# v2164_quad_VCA_0402_DIL.net
KiCad netlist of a schematic drawn in EAGLE
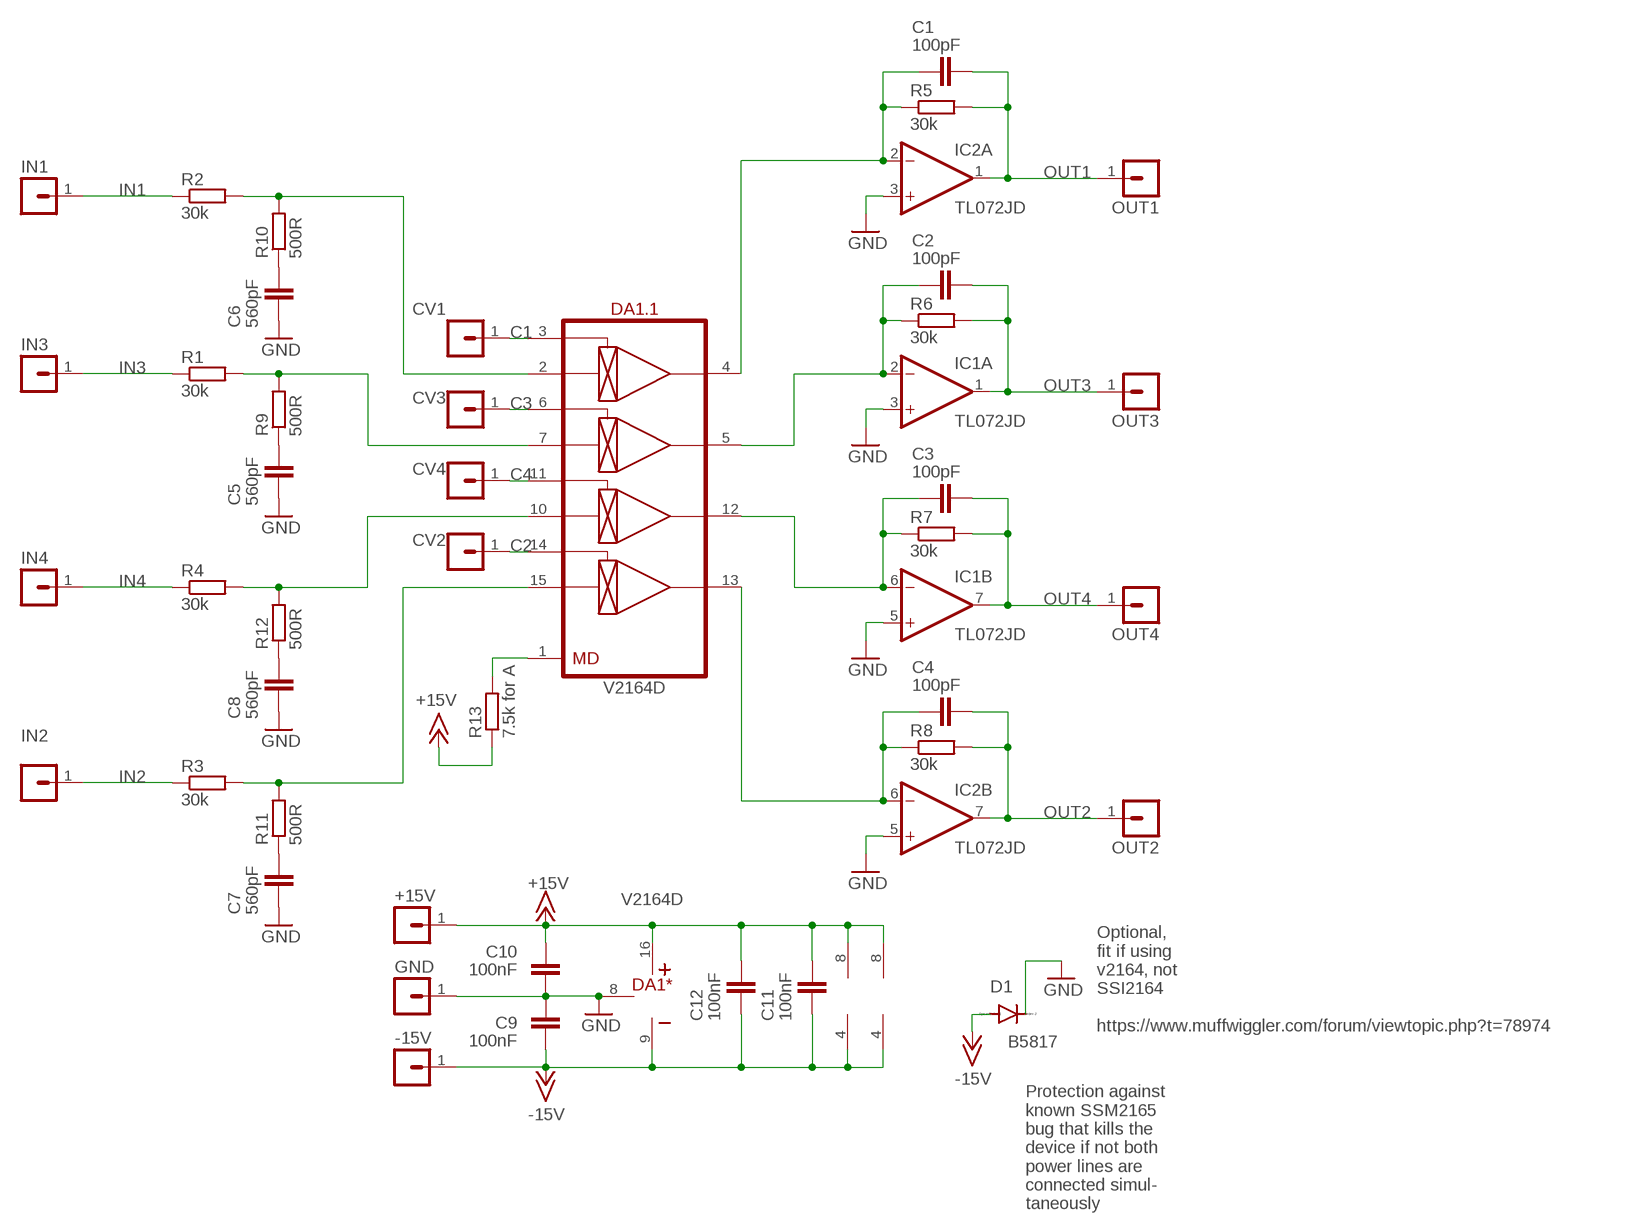
[diagram p0: schematic, sheet 1]

(export (version "E")
  (design (tool "Eeschema 10.0.6"))
  (components
    (comp (ref "+15V")
      (value "MA01-1JP")
      (footprint "eagle-import:SIP-PIN01-1J")
      (libsource (lib "eagle-import") (part "MA01-1JP"))
    )
    (comp (ref "-15V")
      (value "MA01-1JP")
      (footprint "eagle-import:SIP-PIN01-1J")
      (libsource (lib "eagle-import") (part "MA01-1JP"))
    )
    (comp (ref "C1")
      (value "100pF")
      (footprint "eagle-import:C0402")
      (libsource (lib "eagle-import") (part "C-EUC0402"))
    )
    (comp (ref "C2")
      (value "100pF")
      (footprint "eagle-import:C0402")
      (libsource (lib "eagle-import") (part "C-EUC0402"))
    )
    (comp (ref "C3")
      (value "100pF")
      (footprint "eagle-import:C0402")
      (libsource (lib "eagle-import") (part "C-EUC0402"))
    )
    (comp (ref "C4")
      (value "100pF")
      (footprint "eagle-import:C0402")
      (libsource (lib "eagle-import") (part "C-EUC0402"))
    )
    (comp (ref "C5")
      (value "560pF")
      (footprint "eagle-import:C0603")
      (libsource (lib "eagle-import") (part "C-EUC0603"))
    )
    (comp (ref "C6")
      (value "560pF")
      (footprint "eagle-import:C0603")
      (libsource (lib "eagle-import") (part "C-EUC0603"))
    )
    (comp (ref "C7")
      (value "560pF")
      (footprint "eagle-import:C0603")
      (libsource (lib "eagle-import") (part "C-EUC0603"))
    )
    (comp (ref "C8")
      (value "560pF")
      (footprint "eagle-import:C0603")
      (libsource (lib "eagle-import") (part "C-EUC0603"))
    )
    (comp (ref "C9")
      (value "100nF")
      (footprint "eagle-import:C0402")
      (libsource (lib "eagle-import") (part "C-EUC0402"))
    )
    (comp (ref "C10")
      (value "100nF")
      (footprint "eagle-import:C0402")
      (libsource (lib "eagle-import") (part "C-EUC0402"))
    )
    (comp (ref "C11")
      (value "100nF")
      (footprint "eagle-import:C0402")
      (libsource (lib "eagle-import") (part "C-EUC0402"))
    )
    (comp (ref "C12")
      (value "100nF")
      (footprint "eagle-import:C0402")
      (libsource (lib "eagle-import") (part "C-EUC0402"))
    )
    (comp (ref "CV1")
      (value "MA01-1JP")
      (footprint "eagle-import:SIP-PIN01-1J")
      (libsource (lib "eagle-import") (part "MA01-1JP"))
    )
    (comp (ref "CV2")
      (value "MA01-1JP")
      (footprint "eagle-import:SIP-PIN01-1J")
      (libsource (lib "eagle-import") (part "MA01-1JP"))
    )
    (comp (ref "CV3")
      (value "MA01-1JP")
      (footprint "eagle-import:SIP-PIN01-1J")
      (libsource (lib "eagle-import") (part "MA01-1JP"))
    )
    (comp (ref "CV4")
      (value "MA01-1JP")
      (footprint "eagle-import:SIP-PIN01-1J")
      (libsource (lib "eagle-import") (part "MA01-1JP"))
    )
    (comp (ref "D1")
      (value "B5817")
      (footprint "eagle-import:SOD323-R")
      (libsource (lib "eagle-import") (part "DIODE-SOD323-R"))
    )
    (comp (ref "DA1")
      (value "V2164D")
      (footprint "eagle-import:DIP-16")
      (libsource (lib "eagle-import") (part "V2164D"))
    )
    (comp (ref "GND")
      (value "MA01-1JP")
      (footprint "eagle-import:SIP-PIN01-1J")
      (libsource (lib "eagle-import") (part "MA01-1JP"))
    )
    (comp (ref "IC1")
      (value "TL072JD")
      (footprint "eagle-import:SO08J")
      (libsource (lib "eagle-import") (part "TL072JD"))
    )
    (comp (ref "IC2")
      (value "TL072JD")
      (footprint "eagle-import:SO08J")
      (libsource (lib "eagle-import") (part "TL072JD"))
    )
    (comp (ref "IN1")
      (value "MA01-1JP")
      (footprint "eagle-import:SIP-PIN01-1J")
      (libsource (lib "eagle-import") (part "MA01-1JP"))
    )
    (comp (ref "IN2")
      (value "MA01-1JP")
      (footprint "eagle-import:SIP-PIN01-1J")
      (libsource (lib "eagle-import") (part "MA01-1JP"))
    )
    (comp (ref "IN3")
      (value "MA01-1JP")
      (footprint "eagle-import:SIP-PIN01-1J")
      (libsource (lib "eagle-import") (part "MA01-1JP"))
    )
    (comp (ref "IN4")
      (value "MA01-1JP")
      (footprint "eagle-import:SIP-PIN01-1J")
      (libsource (lib "eagle-import") (part "MA01-1JP"))
    )
    (comp (ref "OUT1")
      (value "MA01-1JP")
      (footprint "eagle-import:SIP-PIN01-1J")
      (libsource (lib "eagle-import") (part "MA01-1JP"))
    )
    (comp (ref "OUT2")
      (value "MA01-1JP")
      (footprint "eagle-import:SIP-PIN01-1J")
      (libsource (lib "eagle-import") (part "MA01-1JP"))
    )
    (comp (ref "OUT3")
      (value "MA01-1JP")
      (footprint "eagle-import:SIP-PIN01-1J")
      (libsource (lib "eagle-import") (part "MA01-1JP"))
    )
    (comp (ref "OUT4")
      (value "MA01-1JP")
      (footprint "eagle-import:SIP-PIN01-1J")
      (libsource (lib "eagle-import") (part "MA01-1JP"))
    )
    (comp (ref "R1")
      (value "30k")
      (footprint "eagle-import:R0402")
      (libsource (lib "eagle-import") (part "R-EU_R0402"))
    )
    (comp (ref "R2")
      (value "30k")
      (footprint "eagle-import:R0402")
      (libsource (lib "eagle-import") (part "R-EU_R0402"))
    )
    (comp (ref "R3")
      (value "30k")
      (footprint "eagle-import:R0402")
      (libsource (lib "eagle-import") (part "R-EU_R0402"))
    )
    (comp (ref "R4")
      (value "30k")
      (footprint "eagle-import:R0402")
      (libsource (lib "eagle-import") (part "R-EU_R0402"))
    )
    (comp (ref "R5")
      (value "30k")
      (footprint "eagle-import:R0402")
      (libsource (lib "eagle-import") (part "R-EU_R0402"))
    )
    (comp (ref "R6")
      (value "30k")
      (footprint "eagle-import:R0402")
      (libsource (lib "eagle-import") (part "R-EU_R0402"))
    )
    (comp (ref "R7")
      (value "30k")
      (footprint "eagle-import:R0402")
      (libsource (lib "eagle-import") (part "R-EU_R0402"))
    )
    (comp (ref "R8")
      (value "30k")
      (footprint "eagle-import:R0402")
      (libsource (lib "eagle-import") (part "R-EU_R0402"))
    )
    (comp (ref "R9")
      (value "500R")
      (footprint "eagle-import:R0402")
      (libsource (lib "eagle-import") (part "R-EU_R0402"))
    )
    (comp (ref "R10")
      (value "500R")
      (footprint "eagle-import:R0402")
      (libsource (lib "eagle-import") (part "R-EU_R0402"))
    )
    (comp (ref "R11")
      (value "500R")
      (footprint "eagle-import:R0402")
      (libsource (lib "eagle-import") (part "R-EU_R0402"))
    )
    (comp (ref "R12")
      (value "500R")
      (footprint "eagle-import:R0402")
      (libsource (lib "eagle-import") (part "R-EU_R0402"))
    )
    (comp (ref "R13")
      (value "7.5k for A")
      (footprint "eagle-import:R0402")
      (libsource (lib "eagle-import") (part "R-EU_R0402"))
    )
  )
  (nets
    (net (code "1") (name "+15V") (class "Default")
      (node (ref "+15V") (pin "1") (pinfunction "1_1") (pintype "passive"))
      (node (ref "C10") (pin "2") (pinfunction "2_2") (pintype "passive"))
      (node (ref "C11") (pin "2") (pinfunction "2_2") (pintype "passive"))
      (node (ref "C12") (pin "2") (pinfunction "2_2") (pintype "passive"))
      (node (ref "DA1") (pin "16") (pinfunction "V+_16") (pintype "power_in"))
      (node (ref "IC1") (pin "8") (pinfunction "V+_8") (pintype "power_in"))
      (node (ref "IC2") (pin "8") (pinfunction "V+_8") (pintype "power_in"))
      (node (ref "R13") (pin "1") (pinfunction "1_1") (pintype "passive"))
    )
    (net (code "2") (name "-15V") (class "Default")
      (node (ref "-15V") (pin "1") (pinfunction "1_1") (pintype "passive"))
      (node (ref "C11") (pin "1") (pinfunction "1_1") (pintype "passive"))
      (node (ref "C12") (pin "1") (pinfunction "1_1") (pintype "passive"))
      (node (ref "C9") (pin "1") (pinfunction "1_1") (pintype "passive"))
      (node (ref "D1") (pin "A") (pinfunction "A_A") (pintype "passive"))
      (node (ref "DA1") (pin "9") (pinfunction "V-_9") (pintype "power_in"))
      (node (ref "IC1") (pin "4") (pinfunction "V-_4") (pintype "power_in"))
      (node (ref "IC2") (pin "4") (pinfunction "V-_4") (pintype "power_in"))
    )
    (net (code "3") (name "/C1") (class "Default")
      (node (ref "CV1") (pin "1") (pinfunction "1_1") (pintype "passive"))
      (node (ref "DA1") (pin "3") (pinfunction "CV1_3") (pintype "input"))
    )
    (net (code "4") (name "/C2") (class "Default")
      (node (ref "CV2") (pin "1") (pinfunction "1_1") (pintype "passive"))
      (node (ref "DA1") (pin "14") (pinfunction "CV4_14") (pintype "input"))
    )
    (net (code "5") (name "/C3") (class "Default")
      (node (ref "CV3") (pin "1") (pinfunction "1_1") (pintype "passive"))
      (node (ref "DA1") (pin "6") (pinfunction "CV2_6") (pintype "input"))
    )
    (net (code "6") (name "/C4") (class "Default")
      (node (ref "CV4") (pin "1") (pinfunction "1_1") (pintype "passive"))
      (node (ref "DA1") (pin "11") (pinfunction "CV3_11") (pintype "input"))
    )
    (net (code "7") (name "/IN1") (class "Default")
      (node (ref "IN1") (pin "1") (pinfunction "1_1") (pintype "passive"))
      (node (ref "R2") (pin "1") (pinfunction "1_1") (pintype "passive"))
    )
    (net (code "8") (name "/IN2") (class "Default")
      (node (ref "IN2") (pin "1") (pinfunction "1_1") (pintype "passive"))
      (node (ref "R3") (pin "1") (pinfunction "1_1") (pintype "passive"))
    )
    (net (code "9") (name "/IN3") (class "Default")
      (node (ref "IN3") (pin "1") (pinfunction "1_1") (pintype "passive"))
      (node (ref "R1") (pin "1") (pinfunction "1_1") (pintype "passive"))
    )
    (net (code "10") (name "/IN4") (class "Default")
      (node (ref "IN4") (pin "1") (pinfunction "1_1") (pintype "passive"))
      (node (ref "R4") (pin "1") (pinfunction "1_1") (pintype "passive"))
    )
    (net (code "11") (name "/OUT1") (class "Default")
      (node (ref "C1") (pin "2") (pinfunction "2_2") (pintype "passive"))
      (node (ref "IC2") (pin "1") (pinfunction "OUT_1") (pintype "output"))
      (node (ref "OUT1") (pin "1") (pinfunction "1_1") (pintype "passive"))
      (node (ref "R5") (pin "2") (pinfunction "2_2") (pintype "passive"))
    )
    (net (code "12") (name "/OUT2") (class "Default")
      (node (ref "C4") (pin "2") (pinfunction "2_2") (pintype "passive"))
      (node (ref "IC2") (pin "7") (pinfunction "OUT_7") (pintype "output"))
      (node (ref "OUT2") (pin "1") (pinfunction "1_1") (pintype "passive"))
      (node (ref "R8") (pin "2") (pinfunction "2_2") (pintype "passive"))
    )
    (net (code "13") (name "/OUT3") (class "Default")
      (node (ref "C2") (pin "2") (pinfunction "2_2") (pintype "passive"))
      (node (ref "IC1") (pin "1") (pinfunction "OUT_1") (pintype "output"))
      (node (ref "OUT3") (pin "1") (pinfunction "1_1") (pintype "passive"))
      (node (ref "R6") (pin "2") (pinfunction "2_2") (pintype "passive"))
    )
    (net (code "14") (name "/OUT4") (class "Default")
      (node (ref "C3") (pin "2") (pinfunction "2_2") (pintype "passive"))
      (node (ref "IC1") (pin "7") (pinfunction "OUT_7") (pintype "output"))
      (node (ref "OUT4") (pin "1") (pinfunction "1_1") (pintype "passive"))
      (node (ref "R7") (pin "2") (pinfunction "2_2") (pintype "passive"))
    )
    (net (code "15") (name "GND") (class "Default")
      (node (ref "C10") (pin "1") (pinfunction "1_1") (pintype "passive"))
      (node (ref "C5") (pin "1") (pinfunction "1_1") (pintype "passive"))
      (node (ref "C6") (pin "1") (pinfunction "1_1") (pintype "passive"))
      (node (ref "C7") (pin "1") (pinfunction "1_1") (pintype "passive"))
      (node (ref "C8") (pin "1") (pinfunction "1_1") (pintype "passive"))
      (node (ref "C9") (pin "2") (pinfunction "2_2") (pintype "passive"))
      (node (ref "D1") (pin "C") (pinfunction "C_C") (pintype "passive"))
      (node (ref "DA1") (pin "8") (pinfunction "GND_8") (pintype "power_in"))
      (node (ref "GND") (pin "1") (pinfunction "1_1") (pintype "passive"))
      (node (ref "IC1") (pin "3") (pinfunction "+IN_3") (pintype "input"))
      (node (ref "IC1") (pin "5") (pinfunction "+IN_5") (pintype "input"))
      (node (ref "IC2") (pin "3") (pinfunction "+IN_3") (pintype "input"))
      (node (ref "IC2") (pin "5") (pinfunction "+IN_5") (pintype "input"))
    )
    (net (code "16") (name "Net-(C5-Pad2)") (class "Default")
      (node (ref "C5") (pin "2") (pinfunction "2_2") (pintype "passive"))
      (node (ref "R9") (pin "1") (pinfunction "1_1") (pintype "passive"))
    )
    (net (code "17") (name "Net-(C6-Pad2)") (class "Default")
      (node (ref "C6") (pin "2") (pinfunction "2_2") (pintype "passive"))
      (node (ref "R10") (pin "1") (pinfunction "1_1") (pintype "passive"))
    )
    (net (code "18") (name "Net-(C7-Pad2)") (class "Default")
      (node (ref "C7") (pin "2") (pinfunction "2_2") (pintype "passive"))
      (node (ref "R11") (pin "1") (pinfunction "1_1") (pintype "passive"))
    )
    (net (code "19") (name "Net-(C8-Pad2)") (class "Default")
      (node (ref "C8") (pin "2") (pinfunction "2_2") (pintype "passive"))
      (node (ref "R12") (pin "1") (pinfunction "1_1") (pintype "passive"))
    )
    (net (code "20") (name "Net-(DA1B-IN1)") (class "Default")
      (node (ref "DA1") (pin "2") (pinfunction "IN1_2") (pintype "input"))
      (node (ref "R10") (pin "2") (pinfunction "2_2") (pintype "passive"))
      (node (ref "R2") (pin "2") (pinfunction "2_2") (pintype "passive"))
    )
    (net (code "21") (name "Net-(DA1B-IN2)") (class "Default")
      (node (ref "DA1") (pin "7") (pinfunction "IN2_7") (pintype "input"))
      (node (ref "R1") (pin "2") (pinfunction "2_2") (pintype "passive"))
      (node (ref "R9") (pin "2") (pinfunction "2_2") (pintype "passive"))
    )
    (net (code "22") (name "Net-(DA1B-IN3)") (class "Default")
      (node (ref "DA1") (pin "10") (pinfunction "IN3_10") (pintype "input"))
      (node (ref "R12") (pin "2") (pinfunction "2_2") (pintype "passive"))
      (node (ref "R4") (pin "2") (pinfunction "2_2") (pintype "passive"))
    )
    (net (code "23") (name "Net-(DA1B-IN4)") (class "Default")
      (node (ref "DA1") (pin "15") (pinfunction "IN4_15") (pintype "input"))
      (node (ref "R11") (pin "2") (pinfunction "2_2") (pintype "passive"))
      (node (ref "R3") (pin "2") (pinfunction "2_2") (pintype "passive"))
    )
    (net (code "24") (name "Net-(DA1B-MD)") (class "Default")
      (node (ref "DA1") (pin "1") (pinfunction "MD_1") (pintype "output"))
      (node (ref "R13") (pin "2") (pinfunction "2_2") (pintype "passive"))
    )
    (net (code "25") (name "Net-(DA1B-OUT1)") (class "Default")
      (node (ref "C1") (pin "1") (pinfunction "1_1") (pintype "passive"))
      (node (ref "DA1") (pin "4") (pinfunction "OUT1_4") (pintype "output"))
      (node (ref "IC2") (pin "2") (pinfunction "-IN_2") (pintype "input"))
      (node (ref "R5") (pin "1") (pinfunction "1_1") (pintype "passive"))
    )
    (net (code "26") (name "Net-(DA1B-OUT2)") (class "Default")
      (node (ref "C2") (pin "1") (pinfunction "1_1") (pintype "passive"))
      (node (ref "DA1") (pin "5") (pinfunction "OUT2_5") (pintype "output"))
      (node (ref "IC1") (pin "2") (pinfunction "-IN_2") (pintype "input"))
      (node (ref "R6") (pin "1") (pinfunction "1_1") (pintype "passive"))
    )
    (net (code "27") (name "Net-(DA1B-OUT3)") (class "Default")
      (node (ref "C3") (pin "1") (pinfunction "1_1") (pintype "passive"))
      (node (ref "DA1") (pin "12") (pinfunction "OUT3_12") (pintype "output"))
      (node (ref "IC1") (pin "6") (pinfunction "-IN_6") (pintype "input"))
      (node (ref "R7") (pin "1") (pinfunction "1_1") (pintype "passive"))
    )
    (net (code "28") (name "Net-(DA1B-OUT4)") (class "Default")
      (node (ref "C4") (pin "1") (pinfunction "1_1") (pintype "passive"))
      (node (ref "DA1") (pin "13") (pinfunction "OUT4_13") (pintype "output"))
      (node (ref "IC2") (pin "6") (pinfunction "-IN_6") (pintype "input"))
      (node (ref "R8") (pin "1") (pinfunction "1_1") (pintype "passive"))
    )
  )
)
